# schematic.net
KiCad netlist of a schematic drawn in EasyEDA
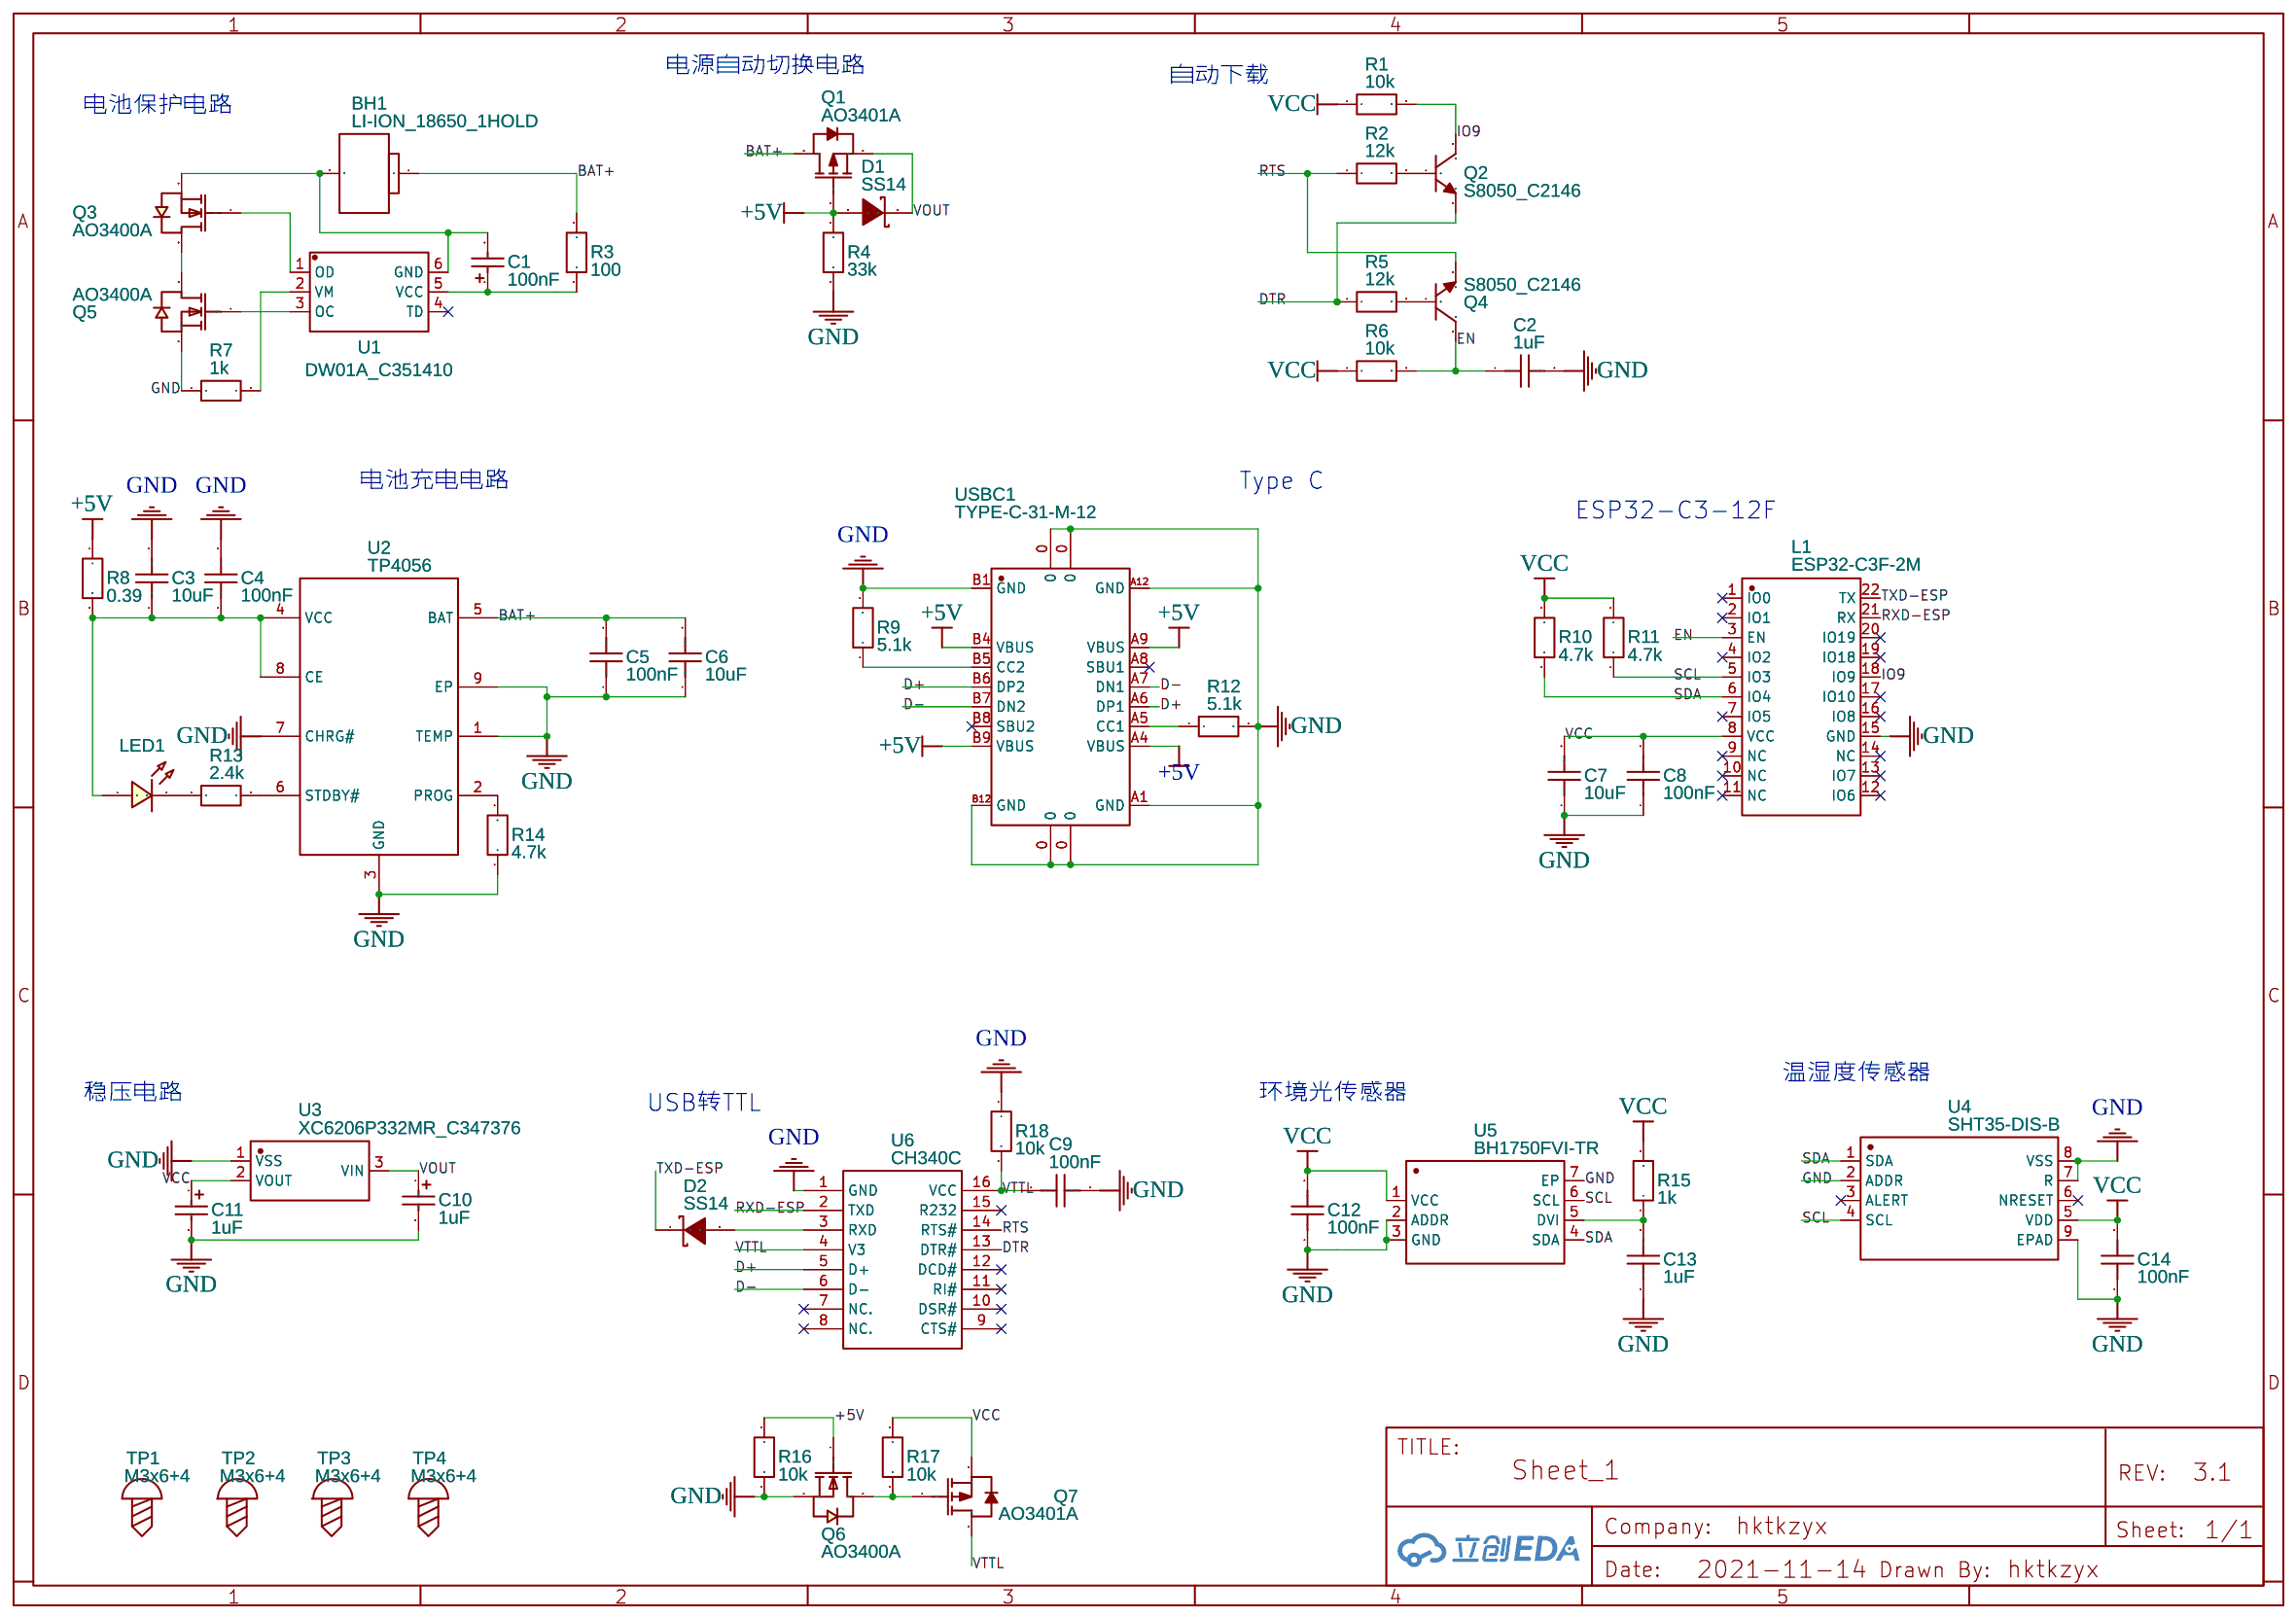
[diagram p0: schematic sheet]

(export (version "E")
  (design (tool "Eeschema 10.0.6"))
  (components
    (comp (ref "BH1")
      (value "LI-ION_18650_1HOLD")
      (fields (field (name "BOM_Manufacturer Part") "BH18650-PC2"))
      (libsource (lib "") (part "LI-ION_18650_1HOLD"))
    )
    (comp (ref "C1")
      (value "100nF")
      (fields
        (field (name "BOM_Manufacturer Part") "TAJA104K035RNJ")
        (field (name "BOM_Supplier Part") "C7173")
      )
      (libsource (lib "") (part "TAJA104K035RNJ"))
    )
    (comp (ref "C2")
      (value "1uF")
      (fields
        (field (name "BOM_Manufacturer Part") "CL10A105KB8NNNC")
        (field (name "BOM_Supplier Part") "C15849")
      )
      (libsource (lib "") (part "C_0603_US_1"))
    )
    (comp (ref "C3")
      (value "10uF")
      (fields
        (field (name "BOM_Manufacturer Part") "CL10A106KP8NNNC")
        (field (name "BOM_Supplier Part") "C19702")
      )
      (libsource (lib "") (part "C_0603_US"))
    )
    (comp (ref "C4")
      (value "100nF")
      (fields
        (field (name "BOM_Manufacturer Part") "CC0603KRX7R9BB104")
        (field (name "BOM_Supplier Part") "C14663")
      )
      (libsource (lib "") (part "C_0603_US"))
    )
    (comp (ref "C5")
      (value "100nF")
      (fields
        (field (name "BOM_Manufacturer Part") "CC0603KRX7R9BB104")
        (field (name "BOM_Supplier Part") "C14663")
      )
      (libsource (lib "") (part "C_0603_US"))
    )
    (comp (ref "C6")
      (value "10uF")
      (fields
        (field (name "BOM_Manufacturer Part") "CL10A106KP8NNNC")
        (field (name "BOM_Supplier Part") "C19702")
      )
      (libsource (lib "") (part "C_0603_US"))
    )
    (comp (ref "C7")
      (value "10uF")
      (fields
        (field (name "BOM_Manufacturer Part") "CL10A106KP8NNNC")
        (field (name "BOM_Supplier Part") "C19702")
      )
      (libsource (lib "") (part "C_0603_US"))
    )
    (comp (ref "C8")
      (value "100nF")
      (fields
        (field (name "BOM_Manufacturer Part") "CC0603KRX7R9BB104")
        (field (name "BOM_Supplier Part") "C14663")
      )
      (libsource (lib "") (part "C_0603_US"))
    )
    (comp (ref "C9")
      (value "100nF")
      (fields
        (field (name "BOM_Manufacturer Part") "CC0603KRX7R9BB104")
        (field (name "BOM_Supplier Part") "C14663")
      )
      (libsource (lib "") (part "C_0603_US_1"))
    )
    (comp (ref "C10")
      (value "1uF")
      (fields
        (field (name "BOM_Manufacturer Part") "TAJA105K016RNJ")
        (field (name "BOM_Supplier Part") "C7174")
      )
      (libsource (lib "") (part "TAJA105K016RNJ"))
    )
    (comp (ref "C11")
      (value "1uF")
      (fields
        (field (name "BOM_Manufacturer Part") "TAJA105K016RNJ")
        (field (name "BOM_Supplier Part") "C7174")
      )
      (libsource (lib "") (part "TAJA105K016RNJ"))
    )
    (comp (ref "C12")
      (value "100nF")
      (fields
        (field (name "BOM_Manufacturer Part") "CC0603KRX7R9BB104")
        (field (name "BOM_Supplier Part") "C14663")
      )
      (libsource (lib "") (part "C_0603_US"))
    )
    (comp (ref "C13")
      (value "1uF")
      (fields
        (field (name "BOM_Manufacturer Part") "CL10A105KB8NNNC")
        (field (name "BOM_Supplier Part") "C15849")
      )
      (libsource (lib "") (part "C_0603_US"))
    )
    (comp (ref "C14")
      (value "100nF")
      (fields
        (field (name "BOM_Manufacturer Part") "CC0603KRX7R9BB104")
        (field (name "BOM_Supplier Part") "C14663")
      )
      (libsource (lib "") (part "C_0603_US"))
    )
    (comp (ref "D1")
      (value "SS14")
      (fields (field (name "BOM_Supplier Part") "C2480"))
      (libsource (lib "") (part "SS14"))
    )
    (comp (ref "D2")
      (value "SS14")
      (fields (field (name "BOM_Supplier Part") "C2480"))
      (libsource (lib "") (part "SS14_1"))
    )
    (comp (ref "L1")
      (value "ESP32-C3F-2M")
      (fields (field (name "BOM_Supplier Part") "C2830867"))
      (libsource (lib "") (part "ESP32-C3F-2M"))
    )
    (comp (ref "LED1")
      (value "LED-0603_G")
      (fields
        (field (name "BOM_Manufacturer Part") "19-217/GHC-YR1S2/3T")
        (field (name "BOM_Supplier Part") "C72043")
      )
      (libsource (lib "") (part "LED-0603_G"))
    )
    (comp (ref "Q1")
      (value "AO3401A")
      (fields (field (name "BOM_Supplier Part") "C15127"))
      (libsource (lib "") (part "AO3401A_1"))
    )
    (comp (ref "Q2")
      (value "S8050_C2146")
      (fields (field (name "BOM_Manufacturer Part") "S8050") (field (name "BOM_Supplier Part") "C2146"))
      (libsource (lib "") (part "S8050_C2146"))
    )
    (comp (ref "Q3")
      (value "AO3400A")
      (fields (field (name "BOM_Supplier Part") "C20917"))
      (libsource (lib "") (part "AO3400A_2"))
    )
    (comp (ref "Q4")
      (value "S8050_C2146")
      (fields (field (name "BOM_Manufacturer Part") "S8050") (field (name "BOM_Supplier Part") "C2146"))
      (libsource (lib "") (part "S8050_C2146_1"))
    )
    (comp (ref "Q5")
      (value "AO3400A")
      (fields (field (name "BOM_Supplier Part") "C20917"))
      (libsource (lib "") (part "AO3400A"))
    )
    (comp (ref "Q6")
      (value "AO3400A")
      (fields (field (name "BOM_Supplier Part") "C20917"))
      (libsource (lib "") (part "AO3400A_1"))
    )
    (comp (ref "Q7")
      (value "AO3401A")
      (fields (field (name "BOM_Supplier Part") "C15127"))
      (libsource (lib "") (part "AO3401A"))
    )
    (comp (ref "R1")
      (value "10k")
      (fields
        (field (name "BOM_Manufacturer Part") "0603WAF1002T5E")
        (field (name "BOM_Supplier Part") "C25804")
      )
      (libsource (lib "") (part "R_0603_EU_1"))
    )
    (comp (ref "R2")
      (value "12k")
      (fields
        (field (name "BOM_Manufacturer Part") "0603WAF1202T5E")
        (field (name "BOM_Supplier Part") "C22790")
      )
      (libsource (lib "") (part "R_0603_EU_1"))
    )
    (comp (ref "R3")
      (value "100")
      (fields
        (field (name "BOM_Manufacturer Part") "0603WAF1000T5E")
        (field (name "BOM_Supplier Part") "C22775")
      )
      (libsource (lib "") (part "R_0603_EU"))
    )
    (comp (ref "R4")
      (value "33k")
      (fields
        (field (name "BOM_Manufacturer Part") "0603WAF3302T5E")
        (field (name "BOM_Supplier Part") "C4216")
      )
      (libsource (lib "") (part "R_0603_EU"))
    )
    (comp (ref "R5")
      (value "12k")
      (fields
        (field (name "BOM_Manufacturer Part") "0603WAF1202T5E")
        (field (name "BOM_Supplier Part") "C22790")
      )
      (libsource (lib "") (part "R_0603_EU_1"))
    )
    (comp (ref "R6")
      (value "10k")
      (fields
        (field (name "BOM_Manufacturer Part") "0603WAF1002T5E")
        (field (name "BOM_Supplier Part") "C25804")
      )
      (libsource (lib "") (part "R_0603_EU_1"))
    )
    (comp (ref "R7")
      (value "1k")
      (fields
        (field (name "BOM_Manufacturer Part") "0603WAF1001T5E")
        (field (name "BOM_Supplier Part") "C21190")
      )
      (libsource (lib "") (part "R_0603_EU_1"))
    )
    (comp (ref "R8")
      (value "0.39")
      (fields
        (field (name "BOM_Manufacturer Part") "RTT20R390FTE")
        (field (name "BOM_Supplier Part") "C159205")
      )
      (libsource (lib "") (part "R_2010_EU"))
    )
    (comp (ref "R9")
      (value "5.1k")
      (fields
        (field (name "BOM_Manufacturer Part") "0603WAF5101T5E")
        (field (name "BOM_Supplier Part") "C23186")
      )
      (libsource (lib "") (part "R_0603_EU"))
    )
    (comp (ref "R10")
      (value "4.7k")
      (fields
        (field (name "BOM_Manufacturer Part") "0603WAF4701T5E")
        (field (name "BOM_Supplier Part") "C23162")
      )
      (libsource (lib "") (part "R_0603_EU"))
    )
    (comp (ref "R11")
      (value "4.7k")
      (fields
        (field (name "BOM_Manufacturer Part") "0603WAF4701T5E")
        (field (name "BOM_Supplier Part") "C23162")
      )
      (libsource (lib "") (part "R_0603_EU"))
    )
    (comp (ref "R12")
      (value "5.1k")
      (fields
        (field (name "BOM_Manufacturer Part") "0603WAF5101T5E")
        (field (name "BOM_Supplier Part") "C23186")
      )
      (libsource (lib "") (part "R_0603_EU_1"))
    )
    (comp (ref "R13")
      (value "2.4k")
      (fields
        (field (name "BOM_Manufacturer Part") "0603WAF2401T5E")
        (field (name "BOM_Supplier Part") "C22940")
      )
      (libsource (lib "") (part "R_0603_EU_1"))
    )
    (comp (ref "R14")
      (value "4.7k")
      (fields
        (field (name "BOM_Manufacturer Part") "0603WAF4701T5E")
        (field (name "BOM_Supplier Part") "C23162")
      )
      (libsource (lib "") (part "R_0603_EU"))
    )
    (comp (ref "R15")
      (value "1k")
      (fields
        (field (name "BOM_Manufacturer Part") "0603WAF1001T5E")
        (field (name "BOM_Supplier Part") "C21190")
      )
      (libsource (lib "") (part "R_0603_EU"))
    )
    (comp (ref "R16")
      (value "10k")
      (fields
        (field (name "BOM_Manufacturer Part") "0603WAF1002T5E")
        (field (name "BOM_Supplier Part") "C25804")
      )
      (libsource (lib "") (part "R_0603_EU"))
    )
    (comp (ref "R17")
      (value "10k")
      (fields
        (field (name "BOM_Manufacturer Part") "0603WAF1002T5E")
        (field (name "BOM_Supplier Part") "C25804")
      )
      (libsource (lib "") (part "R_0603_EU"))
    )
    (comp (ref "R18")
      (value "10k")
      (fields
        (field (name "BOM_Manufacturer Part") "0603WAF1002T5E")
        (field (name "BOM_Supplier Part") "C25804")
      )
      (libsource (lib "") (part "R_0603_EU_2"))
    )
    (comp (ref "TP1")
      (value "M3x6+4")
      (fields (field (name "BOM_Supplier Part") "C551320"))
      (libsource (lib "") (part "M3x6+4_1"))
    )
    (comp (ref "TP2")
      (value "M3x6+4")
      (fields (field (name "BOM_Supplier Part") "C551320"))
      (libsource (lib "") (part "M3x6+4_2"))
    )
    (comp (ref "TP3")
      (value "M3x6+4")
      (fields (field (name "BOM_Supplier Part") "C551320"))
      (libsource (lib "") (part "M3x6+4"))
    )
    (comp (ref "TP4")
      (value "M3x6+4")
      (fields (field (name "BOM_Supplier Part") "C551320"))
      (libsource (lib "") (part "M3x6+4_1"))
    )
    (comp (ref "U1")
      (value "DW01A_C351410")
      (fields (field (name "BOM_Manufacturer Part") "DW01A") (field (name "BOM_Supplier Part") "C351410"))
      (libsource (lib "") (part "DW01A_C351410"))
    )
    (comp (ref "U2")
      (value "TP4056")
      (fields (field (name "BOM_Supplier Part") "C16581"))
      (libsource (lib "") (part "TP4056"))
    )
    (comp (ref "U3")
      (value "XC6206P332MR_C347376")
      (fields
        (field (name "BOM_Manufacturer Part") "XC6206P332MR")
        (field (name "BOM_Supplier Part") "C347376")
      )
      (libsource (lib "") (part "XC6206P332MR_C347376"))
    )
    (comp (ref "U4")
      (value "SHT35-DIS-B")
      (fields (field (name "BOM_Supplier Part") "C90161"))
      (libsource (lib "") (part "SHT35-DIS-B"))
    )
    (comp (ref "U5")
      (value "BH1750FVI-TR")
      (fields (field (name "BOM_Supplier Part") "C78960"))
      (libsource (lib "") (part "BH1750FVI-TR"))
    )
    (comp (ref "U6")
      (value "CH340C")
      (fields (field (name "BOM_Supplier Part") "C84681"))
      (libsource (lib "") (part "CH340C"))
    )
    (comp (ref "USBC1")
      (value "TYPE-C-31-M-12")
      (fields (field (name "BOM_Supplier Part") "C165948"))
      (libsource (lib "") (part "TYPE-C-31-M-12"))
    )
  )
  (nets
    (net (code "1") (name "+5V") (class "Default")
      (node (ref "D1") (pin "2") (pinfunction "A_2") (pintype "unspecified"))
      (node (ref "Q1") (pin "1") (pinfunction "G_1") (pintype "unspecified"))
      (node (ref "Q6") (pin "1") (pinfunction "G_1") (pintype "unspecified"))
      (node (ref "R16") (pin "2") (pinfunction "2_2") (pintype "unspecified"))
      (node (ref "R4") (pin "2") (pinfunction "2_2") (pintype "unspecified"))
      (node (ref "R8") (pin "1") (pinfunction "1_1") (pintype "unspecified"))
      (node (ref "USBC1") (pin "A4") (pinfunction "VBUS_A4") (pintype "unspecified"))
      (node (ref "USBC1") (pin "A9") (pinfunction "VBUS_A9") (pintype "unspecified"))
      (node (ref "USBC1") (pin "B4") (pinfunction "VBUS_B4") (pintype "unspecified"))
      (node (ref "USBC1") (pin "B9") (pinfunction "VBUS_B9") (pintype "unspecified"))
    )
    (net (code "2") (name "/BAT+") (class "Default")
      (node (ref "BH1") (pin "1") (pinfunction "1_1") (pintype "unspecified"))
      (node (ref "C5") (pin "2") (pinfunction "2_2") (pintype "unspecified"))
      (node (ref "C6") (pin "2") (pinfunction "2_2") (pintype "unspecified"))
      (node (ref "Q1") (pin "3") (pinfunction "D_3") (pintype "unspecified"))
      (node (ref "R3") (pin "2") (pinfunction "2_2") (pintype "unspecified"))
      (node (ref "U2") (pin "5") (pinfunction "BAT_5") (pintype "unspecified"))
    )
    (net (code "3") (name "/D+") (class "Default")
      (node (ref "U6") (pin "5") (pinfunction "D+_5") (pintype "unspecified"))
      (node (ref "USBC1") (pin "A6") (pinfunction "DP1_A6") (pintype "unspecified"))
      (node (ref "USBC1") (pin "B6") (pinfunction "DP2_B6") (pintype "unspecified"))
    )
    (net (code "4") (name "/D-") (class "Default")
      (node (ref "U6") (pin "6") (pinfunction "D-_6") (pintype "unspecified"))
      (node (ref "USBC1") (pin "A7") (pinfunction "DN1_A7") (pintype "unspecified"))
      (node (ref "USBC1") (pin "B7") (pinfunction "DN2_B7") (pintype "unspecified"))
    )
    (net (code "5") (name "/DTR") (class "Default")
      (node (ref "Q2") (pin "2") (pinfunction "E_2") (pintype "unspecified"))
      (node (ref "R5") (pin "1") (pinfunction "1_1") (pintype "unspecified"))
      (node (ref "U6") (pin "13") (pinfunction "DTR#_13") (pintype "unspecified"))
    )
    (net (code "6") (name "/EN") (class "Default")
      (node (ref "C2") (pin "1") (pinfunction "1_1") (pintype "unspecified"))
      (node (ref "L1") (pin "3") (pinfunction "EN_3") (pintype "unspecified"))
      (node (ref "Q4") (pin "3") (pinfunction "C_3") (pintype "unspecified"))
      (node (ref "R6") (pin "2") (pinfunction "2_2") (pintype "unspecified"))
    )
    (net (code "7") (name "/IO9") (class "Default")
      (node (ref "L1") (pin "18") (pinfunction "IO9_18") (pintype "unspecified"))
      (node (ref "Q2") (pin "3") (pinfunction "C_3") (pintype "unspecified"))
      (node (ref "R1") (pin "2") (pinfunction "2_2") (pintype "unspecified"))
    )
    (net (code "8") (name "/RTS") (class "Default")
      (node (ref "Q4") (pin "2") (pinfunction "E_2") (pintype "unspecified"))
      (node (ref "R2") (pin "1") (pinfunction "1_1") (pintype "unspecified"))
      (node (ref "U6") (pin "14") (pinfunction "RTS#_14") (pintype "unspecified"))
    )
    (net (code "9") (name "/RXD-ESP") (class "Default")
      (node (ref "L1") (pin "21") (pinfunction "RX_21") (pintype "unspecified"))
      (node (ref "U6") (pin "2") (pinfunction "TXD_2") (pintype "unspecified"))
    )
    (net (code "10") (name "/SCL") (class "Default")
      (node (ref "L1") (pin "5") (pinfunction "IO3_5") (pintype "unspecified"))
      (node (ref "R11") (pin "1") (pinfunction "1_1") (pintype "unspecified"))
      (node (ref "U4") (pin "4") (pinfunction "SCL_4") (pintype "unspecified"))
      (node (ref "U5") (pin "6") (pinfunction "SCL_6") (pintype "unspecified"))
    )
    (net (code "11") (name "/SDA") (class "Default")
      (node (ref "L1") (pin "6") (pinfunction "IO4_6") (pintype "unspecified"))
      (node (ref "R10") (pin "1") (pinfunction "1_1") (pintype "unspecified"))
      (node (ref "U4") (pin "1") (pinfunction "SDA_1") (pintype "unspecified"))
      (node (ref "U5") (pin "4") (pinfunction "SDA_4") (pintype "unspecified"))
    )
    (net (code "12") (name "/TXD-ESP") (class "Default")
      (node (ref "D2") (pin "1") (pinfunction "K_1") (pintype "unspecified"))
      (node (ref "L1") (pin "22") (pinfunction "TX_22") (pintype "unspecified"))
    )
    (net (code "13") (name "/VOUT") (class "Default")
      (node (ref "C10") (pin "1") (pinfunction "1_1") (pintype "input"))
      (node (ref "D1") (pin "1") (pinfunction "K_1") (pintype "unspecified"))
      (node (ref "Q1") (pin "2") (pinfunction "S_2") (pintype "unspecified"))
      (node (ref "U3") (pin "3") (pinfunction "VIN_3") (pintype "unspecified"))
    )
    (net (code "14") (name "/VTTL") (class "Default")
      (node (ref "C9") (pin "1") (pinfunction "1_1") (pintype "unspecified"))
      (node (ref "Q7") (pin "3") (pinfunction "D_3") (pintype "unspecified"))
      (node (ref "R18") (pin "2") (pinfunction "2_2") (pintype "unspecified"))
      (node (ref "U6") (pin "16") (pinfunction "VCC_16") (pintype "unspecified"))
      (node (ref "U6") (pin "4") (pinfunction "V3_4") (pintype "unspecified"))
    )
    (net (code "15") (name "GND") (class "Default")
      (node (ref "C10") (pin "2") (pinfunction "2_2") (pintype "input"))
      (node (ref "C11") (pin "2") (pinfunction "2_2") (pintype "input"))
      (node (ref "C12") (pin "1") (pinfunction "1_1") (pintype "unspecified"))
      (node (ref "C13") (pin "1") (pinfunction "1_1") (pintype "unspecified"))
      (node (ref "C14") (pin "1") (pinfunction "1_1") (pintype "unspecified"))
      (node (ref "C2") (pin "2") (pinfunction "2_2") (pintype "unspecified"))
      (node (ref "C3") (pin "2") (pinfunction "2_2") (pintype "unspecified"))
      (node (ref "C4") (pin "2") (pinfunction "2_2") (pintype "unspecified"))
      (node (ref "C5") (pin "1") (pinfunction "1_1") (pintype "unspecified"))
      (node (ref "C6") (pin "1") (pinfunction "1_1") (pintype "unspecified"))
      (node (ref "C7") (pin "1") (pinfunction "1_1") (pintype "unspecified"))
      (node (ref "C8") (pin "1") (pinfunction "1_1") (pintype "unspecified"))
      (node (ref "C9") (pin "2") (pinfunction "2_2") (pintype "unspecified"))
      (node (ref "L1") (pin "15") (pinfunction "GND_15") (pintype "unspecified"))
      (node (ref "Q5") (pin "2") (pinfunction "S_2") (pintype "unspecified"))
      (node (ref "Q6") (pin "2") (pinfunction "S_2") (pintype "unspecified"))
      (node (ref "R12") (pin "2") (pinfunction "2_2") (pintype "unspecified"))
      (node (ref "R14") (pin "1") (pinfunction "1_1") (pintype "unspecified"))
      (node (ref "R16") (pin "1") (pinfunction "1_1") (pintype "unspecified"))
      (node (ref "R18") (pin "1") (pinfunction "1_1") (pintype "unspecified"))
      (node (ref "R4") (pin "1") (pinfunction "1_1") (pintype "unspecified"))
      (node (ref "R7") (pin "1") (pinfunction "1_1") (pintype "unspecified"))
      (node (ref "R9") (pin "2") (pinfunction "2_2") (pintype "unspecified"))
      (node (ref "U2") (pin "1") (pinfunction "TEMP_1") (pintype "unspecified"))
      (node (ref "U2") (pin "3") (pinfunction "GND_3") (pintype "unspecified"))
      (node (ref "U2") (pin "7") (pinfunction "CHRG#_7") (pintype "unspecified"))
      (node (ref "U2") (pin "9") (pinfunction "EP_9") (pintype "unspecified"))
      (node (ref "U3") (pin "1") (pinfunction "VSS_1") (pintype "unspecified"))
      (node (ref "U4") (pin "2") (pinfunction "ADDR_2") (pintype "unspecified"))
      (node (ref "U4") (pin "7") (pinfunction "R_7") (pintype "unspecified"))
      (node (ref "U4") (pin "8") (pinfunction "VSS_8") (pintype "unspecified"))
      (node (ref "U4") (pin "9") (pinfunction "EPAD_9") (pintype "unspecified"))
      (node (ref "U5") (pin "2") (pinfunction "ADDR_2") (pintype "unspecified"))
      (node (ref "U5") (pin "3") (pinfunction "GND_3") (pintype "unspecified"))
      (node (ref "U5") (pin "7") (pinfunction "EP_7") (pintype "unspecified"))
      (node (ref "U6") (pin "1") (pinfunction "GND_1") (pintype "unspecified"))
      (node (ref "USBC1") (pin "0") (pinfunction "0_0") (pintype "unspecified"))
      (node (ref "USBC1") (pin "A1") (pinfunction "GND_A1") (pintype "unspecified"))
      (node (ref "USBC1") (pin "A12") (pinfunction "GND_A12") (pintype "unspecified"))
      (node (ref "USBC1") (pin "B1") (pinfunction "GND_B1") (pintype "unspecified"))
      (node (ref "USBC1") (pin "B12") (pinfunction "GND_B12") (pintype "unspecified"))
    )
    (net (code "16") (name "Net-(D2-A)") (class "Default")
      (node (ref "D2") (pin "2") (pinfunction "A_2") (pintype "unspecified"))
      (node (ref "U6") (pin "3") (pinfunction "RXD_3") (pintype "unspecified"))
    )
    (net (code "17") (name "Net-(LED1-Pad2)") (class "Default")
      (node (ref "LED1") (pin "2") (pinfunction "2_2") (pintype "unspecified"))
      (node (ref "R13") (pin "1") (pinfunction "1_1") (pintype "unspecified"))
    )
    (net (code "18") (name "Net-(Q2-B)") (class "Default")
      (node (ref "Q2") (pin "1") (pinfunction "B_1") (pintype "unspecified"))
      (node (ref "R2") (pin "2") (pinfunction "2_2") (pintype "unspecified"))
    )
    (net (code "19") (name "Net-(Q3-D)") (class "Default")
      (node (ref "Q3") (pin "3") (pinfunction "D_3") (pintype "unspecified"))
      (node (ref "Q5") (pin "3") (pinfunction "D_3") (pintype "unspecified"))
    )
    (net (code "20") (name "Net-(Q3-G)") (class "Default")
      (node (ref "Q3") (pin "1") (pinfunction "G_1") (pintype "unspecified"))
      (node (ref "U1") (pin "1") (pinfunction "OD_1") (pintype "unspecified"))
    )
    (net (code "21") (name "Net-(Q3-S)") (class "Default")
      (node (ref "BH1") (pin "2") (pinfunction "2_2") (pintype "unspecified"))
      (node (ref "C1") (pin "2") (pinfunction "2_2") (pintype "input"))
      (node (ref "Q3") (pin "2") (pinfunction "S_2") (pintype "unspecified"))
      (node (ref "U1") (pin "6") (pinfunction "GND_6") (pintype "unspecified"))
    )
    (net (code "22") (name "Net-(Q4-B)") (class "Default")
      (node (ref "Q4") (pin "1") (pinfunction "B_1") (pintype "unspecified"))
      (node (ref "R5") (pin "2") (pinfunction "2_2") (pintype "unspecified"))
    )
    (net (code "23") (name "Net-(Q5-G)") (class "Default")
      (node (ref "Q5") (pin "1") (pinfunction "G_1") (pintype "unspecified"))
      (node (ref "U1") (pin "3") (pinfunction "OC_3") (pintype "unspecified"))
    )
    (net (code "24") (name "Net-(Q6-D)") (class "Default")
      (node (ref "Q6") (pin "3") (pinfunction "D_3") (pintype "unspecified"))
      (node (ref "Q7") (pin "1") (pinfunction "G_1") (pintype "unspecified"))
      (node (ref "R17") (pin "1") (pinfunction "1_1") (pintype "unspecified"))
    )
    (net (code "25") (name "Net-(U1-VCC)") (class "Default")
      (node (ref "C1") (pin "1") (pinfunction "1_1") (pintype "input"))
      (node (ref "R3") (pin "1") (pinfunction "1_1") (pintype "unspecified"))
      (node (ref "U1") (pin "5") (pinfunction "VCC_5") (pintype "unspecified"))
    )
    (net (code "26") (name "Net-(U1-VM)") (class "Default")
      (node (ref "R7") (pin "2") (pinfunction "2_2") (pintype "unspecified"))
      (node (ref "U1") (pin "2") (pinfunction "VM_2") (pintype "unspecified"))
    )
    (net (code "27") (name "Net-(U2-CE)") (class "Default")
      (node (ref "C3") (pin "1") (pinfunction "1_1") (pintype "unspecified"))
      (node (ref "C4") (pin "1") (pinfunction "1_1") (pintype "unspecified"))
      (node (ref "LED1") (pin "1") (pinfunction "1_1") (pintype "unspecified"))
      (node (ref "R8") (pin "2") (pinfunction "2_2") (pintype "unspecified"))
      (node (ref "U2") (pin "4") (pinfunction "VCC_4") (pintype "unspecified"))
      (node (ref "U2") (pin "8") (pinfunction "CE_8") (pintype "unspecified"))
    )
    (net (code "28") (name "Net-(U2-PROG)") (class "Default")
      (node (ref "R14") (pin "2") (pinfunction "2_2") (pintype "unspecified"))
      (node (ref "U2") (pin "2") (pinfunction "PROG_2") (pintype "unspecified"))
    )
    (net (code "29") (name "Net-(U2-STDBY#)") (class "Default")
      (node (ref "R13") (pin "2") (pinfunction "2_2") (pintype "unspecified"))
      (node (ref "U2") (pin "6") (pinfunction "STDBY#_6") (pintype "unspecified"))
    )
    (net (code "30") (name "Net-(U5-DVI)") (class "Default")
      (node (ref "C13") (pin "2") (pinfunction "2_2") (pintype "unspecified"))
      (node (ref "R15") (pin "1") (pinfunction "1_1") (pintype "unspecified"))
      (node (ref "U5") (pin "5") (pinfunction "DVI_5") (pintype "unspecified"))
    )
    (net (code "31") (name "Net-(USBC1-CC1)") (class "Default")
      (node (ref "R12") (pin "1") (pinfunction "1_1") (pintype "unspecified"))
      (node (ref "USBC1") (pin "A5") (pinfunction "CC1_A5") (pintype "unspecified"))
    )
    (net (code "32") (name "Net-(USBC1-CC2)") (class "Default")
      (node (ref "R9") (pin "1") (pinfunction "1_1") (pintype "unspecified"))
      (node (ref "USBC1") (pin "B5") (pinfunction "CC2_B5") (pintype "unspecified"))
    )
    (net (code "33") (name "VCC") (class "Default")
      (node (ref "C11") (pin "1") (pinfunction "1_1") (pintype "input"))
      (node (ref "C12") (pin "2") (pinfunction "2_2") (pintype "unspecified"))
      (node (ref "C14") (pin "2") (pinfunction "2_2") (pintype "unspecified"))
      (node (ref "C7") (pin "2") (pinfunction "2_2") (pintype "unspecified"))
      (node (ref "C8") (pin "2") (pinfunction "2_2") (pintype "unspecified"))
      (node (ref "L1") (pin "8") (pinfunction "VCC_8") (pintype "unspecified"))
      (node (ref "Q7") (pin "2") (pinfunction "S_2") (pintype "unspecified"))
      (node (ref "R1") (pin "1") (pinfunction "1_1") (pintype "unspecified"))
      (node (ref "R10") (pin "2") (pinfunction "2_2") (pintype "unspecified"))
      (node (ref "R11") (pin "2") (pinfunction "2_2") (pintype "unspecified"))
      (node (ref "R15") (pin "2") (pinfunction "2_2") (pintype "unspecified"))
      (node (ref "R17") (pin "2") (pinfunction "2_2") (pintype "unspecified"))
      (node (ref "R6") (pin "1") (pinfunction "1_1") (pintype "unspecified"))
      (node (ref "U3") (pin "2") (pinfunction "VOUT_2") (pintype "unspecified"))
      (node (ref "U4") (pin "5") (pinfunction "VDD_5") (pintype "unspecified"))
      (node (ref "U5") (pin "1") (pinfunction "VCC_1") (pintype "unspecified"))
    )
    (net (code "34") (name "unconnected-(L1-IO0-Pad1)") (class "Default")
      (node (ref "L1") (pin "1") (pinfunction "IO0_1") (pintype "unspecified+no_connect"))
    )
    (net (code "35") (name "unconnected-(L1-IO1-Pad2)") (class "Default")
      (node (ref "L1") (pin "2") (pinfunction "IO1_2") (pintype "unspecified+no_connect"))
    )
    (net (code "36") (name "unconnected-(L1-IO2-Pad4)") (class "Default")
      (node (ref "L1") (pin "4") (pinfunction "IO2_4") (pintype "unspecified+no_connect"))
    )
    (net (code "37") (name "unconnected-(L1-IO5-Pad7)") (class "Default")
      (node (ref "L1") (pin "7") (pinfunction "IO5_7") (pintype "unspecified+no_connect"))
    )
    (net (code "38") (name "unconnected-(L1-IO6-Pad12)") (class "Default")
      (node (ref "L1") (pin "12") (pinfunction "IO6_12") (pintype "unspecified+no_connect"))
    )
    (net (code "39") (name "unconnected-(L1-IO7-Pad13)") (class "Default")
      (node (ref "L1") (pin "13") (pinfunction "IO7_13") (pintype "unspecified+no_connect"))
    )
    (net (code "40") (name "unconnected-(L1-IO8-Pad16)") (class "Default")
      (node (ref "L1") (pin "16") (pinfunction "IO8_16") (pintype "unspecified+no_connect"))
    )
    (net (code "41") (name "unconnected-(L1-IO10-Pad17)") (class "Default")
      (node (ref "L1") (pin "17") (pinfunction "IO10_17") (pintype "unspecified+no_connect"))
    )
    (net (code "42") (name "unconnected-(L1-IO18-Pad19)") (class "Default")
      (node (ref "L1") (pin "19") (pinfunction "IO18_19") (pintype "unspecified+no_connect"))
    )
    (net (code "43") (name "unconnected-(L1-IO19-Pad20)") (class "Default")
      (node (ref "L1") (pin "20") (pinfunction "IO19_20") (pintype "unspecified+no_connect"))
    )
    (net (code "44") (name "unconnected-(L1-NC-Pad9)") (class "Default")
      (node (ref "L1") (pin "9") (pinfunction "NC_9") (pintype "unspecified+no_connect"))
    )
    (net (code "45") (name "unconnected-(L1-NC-Pad10)") (class "Default")
      (node (ref "L1") (pin "10") (pinfunction "NC_10") (pintype "unspecified+no_connect"))
    )
    (net (code "46") (name "unconnected-(L1-NC-Pad11)") (class "Default")
      (node (ref "L1") (pin "11") (pinfunction "NC_11") (pintype "unspecified+no_connect"))
    )
    (net (code "47") (name "unconnected-(L1-NC-Pad14)") (class "Default")
      (node (ref "L1") (pin "14") (pinfunction "NC_14") (pintype "unspecified+no_connect"))
    )
    (net (code "48") (name "unconnected-(U1-TD-Pad4)") (class "Default")
      (node (ref "U1") (pin "4") (pinfunction "TD_4") (pintype "unspecified+no_connect"))
    )
    (net (code "49") (name "unconnected-(U4-ALERT-Pad3)") (class "Default")
      (node (ref "U4") (pin "3") (pinfunction "ALERT_3") (pintype "unspecified+no_connect"))
    )
    (net (code "50") (name "unconnected-(U4-NRESET-Pad6)") (class "Default")
      (node (ref "U4") (pin "6") (pinfunction "NRESET_6") (pintype "unspecified+no_connect"))
    )
    (net (code "51") (name "unconnected-(U6-CTS#-Pad9)") (class "Default")
      (node (ref "U6") (pin "9") (pinfunction "CTS#_9") (pintype "unspecified+no_connect"))
    )
    (net (code "52") (name "unconnected-(U6-DCD#-Pad12)") (class "Default")
      (node (ref "U6") (pin "12") (pinfunction "DCD#_12") (pintype "unspecified+no_connect"))
    )
    (net (code "53") (name "unconnected-(U6-DSR#-Pad10)") (class "Default")
      (node (ref "U6") (pin "10") (pinfunction "DSR#_10") (pintype "unspecified+no_connect"))
    )
    (net (code "54") (name "unconnected-(U6-NC.-Pad7)") (class "Default")
      (node (ref "U6") (pin "7") (pinfunction "NC._7") (pintype "unspecified+no_connect"))
    )
    (net (code "55") (name "unconnected-(U6-NC.-Pad8)") (class "Default")
      (node (ref "U6") (pin "8") (pinfunction "NC._8") (pintype "unspecified+no_connect"))
    )
    (net (code "56") (name "unconnected-(U6-R232-Pad15)") (class "Default")
      (node (ref "U6") (pin "15") (pinfunction "R232_15") (pintype "unspecified+no_connect"))
    )
    (net (code "57") (name "unconnected-(U6-RI#-Pad11)") (class "Default")
      (node (ref "U6") (pin "11") (pinfunction "RI#_11") (pintype "unspecified+no_connect"))
    )
    (net (code "58") (name "unconnected-(USBC1-SBU1-PadA8)") (class "Default")
      (node (ref "USBC1") (pin "A8") (pinfunction "SBU1_A8") (pintype "unspecified+no_connect"))
    )
    (net (code "59") (name "unconnected-(USBC1-SBU2-PadB8)") (class "Default")
      (node (ref "USBC1") (pin "B8") (pinfunction "SBU2_B8") (pintype "unspecified+no_connect"))
    )
  )
)
